# coax-adapter.net
KiCad netlist of a schematic drawn in EAGLE
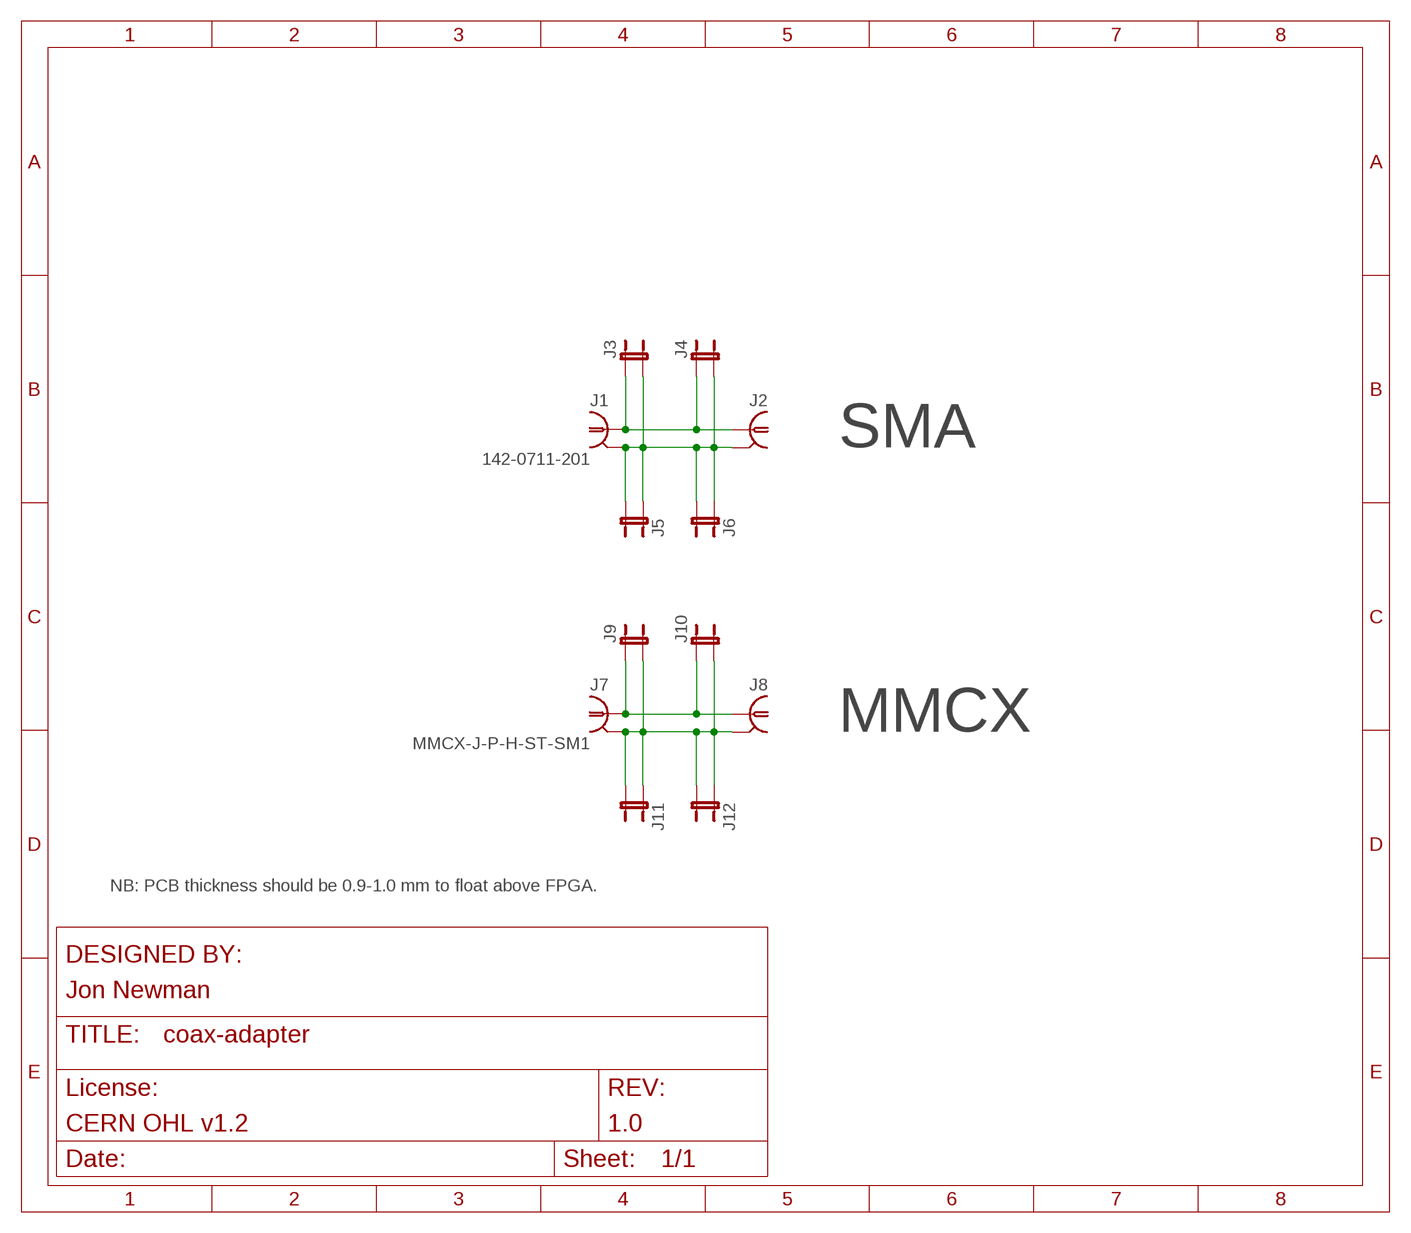
[diagram p0: schematic, sheet 1]

(export (version "E")
  (design (tool "Eeschema 10.0.6"))
  (components
    (comp (ref "J1")
      (value "142-0711-201")
      (footprint "eagle-import:SMA_VERT")
      (libsource (lib "eagle-import") (part "COAX_SMA-VERT-SMA"))
    )
    (comp (ref "J2")
      (value "COAXCOAX-ADAPTER-8X8MM")
      (footprint "eagle-import:COAX-ADAPTER-8X8MM")
      (libsource (lib "eagle-import") (part "COAXCOAX-ADAPTER-8X8MM"))
    )
    (comp (ref "J3")
      (value "JP2E_COAX-ADAPTER-8X8MM-SIG")
      (footprint "eagle-import:COAX-ADAPTER-8X8MM-SIG")
      (libsource (lib "eagle-import") (part "JP2E_COAX-ADAPTER-8X8MM-SIG"))
    )
    (comp (ref "J4")
      (value "JP2E_COAX-ADAPTER-8X8MM-SIG")
      (footprint "eagle-import:COAX-ADAPTER-8X8MM-SIG")
      (libsource (lib "eagle-import") (part "JP2E_COAX-ADAPTER-8X8MM-SIG"))
    )
    (comp (ref "J5")
      (value "JP2E_COAX-ADAPTER-8X8MM-GND")
      (footprint "eagle-import:COAX-ADAPTER-8X8MM-GND")
      (libsource (lib "eagle-import") (part "JP2E_COAX-ADAPTER-8X8MM-GND"))
    )
    (comp (ref "J6")
      (value "JP2E_COAX-ADAPTER-8X8MM-GND")
      (footprint "eagle-import:COAX-ADAPTER-8X8MM-GND")
      (libsource (lib "eagle-import") (part "JP2E_COAX-ADAPTER-8X8MM-GND"))
    )
    (comp (ref "J7")
      (value "MMCX-J-P-H-ST-SM1")
      (footprint "eagle-import:MMCX-SMT-VERT")
      (libsource (lib "eagle-import") (part "COAX_MMCX-VERT"))
    )
    (comp (ref "J8")
      (value "COAXCOAX-ADAPTER-8X8MM")
      (footprint "eagle-import:COAX-ADAPTER-8X8MM")
      (libsource (lib "eagle-import") (part "COAXCOAX-ADAPTER-8X8MM"))
    )
    (comp (ref "J9")
      (value "JP2E_COAX-ADAPTER-8X8MM-SIG")
      (footprint "eagle-import:COAX-ADAPTER-8X8MM-SIG")
      (libsource (lib "eagle-import") (part "JP2E_COAX-ADAPTER-8X8MM-SIG"))
    )
    (comp (ref "J10")
      (value "JP2E_COAX-ADAPTER-8X8MM-SIG")
      (footprint "eagle-import:COAX-ADAPTER-8X8MM-SIG")
      (libsource (lib "eagle-import") (part "JP2E_COAX-ADAPTER-8X8MM-SIG"))
    )
    (comp (ref "J11")
      (value "JP2E_COAX-ADAPTER-8X8MM-GND")
      (footprint "eagle-import:COAX-ADAPTER-8X8MM-GND")
      (libsource (lib "eagle-import") (part "JP2E_COAX-ADAPTER-8X8MM-GND"))
    )
    (comp (ref "J12")
      (value "JP2E_COAX-ADAPTER-8X8MM-GND")
      (footprint "eagle-import:COAX-ADAPTER-8X8MM-GND")
      (libsource (lib "eagle-import") (part "JP2E_COAX-ADAPTER-8X8MM-GND"))
    )
  )
  (nets
    (net (code "1") (name "/ADAPT_SIG") (class "Default")
      (node (ref "J1") (pin "SIG") (pinfunction "1_SIG") (pintype "passive"))
      (node (ref "J10") (pin "SIG") (pinfunction "1_SIG") (pintype "passive"))
      (node (ref "J2") (pin "SIG") (pinfunction "1_SIG") (pintype "passive"))
      (node (ref "J2") (pin "SIGPAD") (pinfunction "1_SIGPAD") (pintype "passive"))
      (node (ref "J3") (pin "SIG") (pinfunction "1_SIG") (pintype "passive"))
      (node (ref "J4") (pin "SIG") (pinfunction "1_SIG") (pintype "passive"))
      (node (ref "J7") (pin "SIG") (pinfunction "1_SIG") (pintype "passive"))
      (node (ref "J8") (pin "SIG") (pinfunction "1_SIG") (pintype "passive"))
      (node (ref "J8") (pin "SIGPAD") (pinfunction "1_SIGPAD") (pintype "passive"))
      (node (ref "J9") (pin "SIG") (pinfunction "1_SIG") (pintype "passive"))
    )
    (net (code "2") (name "/GND") (class "Default")
      (node (ref "J1") (pin "G1") (pinfunction "2_G1") (pintype "passive"))
      (node (ref "J1") (pin "G2") (pinfunction "2_G2") (pintype "passive"))
      (node (ref "J1") (pin "G3") (pinfunction "2_G3") (pintype "passive"))
      (node (ref "J1") (pin "G4") (pinfunction "2_G4") (pintype "passive"))
      (node (ref "J10") (pin "GND1") (pinfunction "2_GND1") (pintype "passive"))
      (node (ref "J10") (pin "GND2") (pinfunction "2_GND2") (pintype "passive"))
      (node (ref "J11") (pin "GND3") (pinfunction "1_GND3") (pintype "passive"))
      (node (ref "J11") (pin "GND4") (pinfunction "2_GND4") (pintype "passive"))
      (node (ref "J12") (pin "GND3") (pinfunction "1_GND3") (pintype "passive"))
      (node (ref "J12") (pin "GND4") (pinfunction "2_GND4") (pintype "passive"))
      (node (ref "J2") (pin "GND1") (pinfunction "2_GND1") (pintype "passive"))
      (node (ref "J2") (pin "GND2") (pinfunction "2_GND2") (pintype "passive"))
      (node (ref "J2") (pin "GND3") (pinfunction "2_GND3") (pintype "passive"))
      (node (ref "J2") (pin "GND4") (pinfunction "2_GND4") (pintype "passive"))
      (node (ref "J3") (pin "GND1") (pinfunction "2_GND1") (pintype "passive"))
      (node (ref "J3") (pin "GND2") (pinfunction "2_GND2") (pintype "passive"))
      (node (ref "J4") (pin "GND1") (pinfunction "2_GND1") (pintype "passive"))
      (node (ref "J4") (pin "GND2") (pinfunction "2_GND2") (pintype "passive"))
      (node (ref "J5") (pin "GND3") (pinfunction "1_GND3") (pintype "passive"))
      (node (ref "J5") (pin "GND4") (pinfunction "2_GND4") (pintype "passive"))
      (node (ref "J6") (pin "GND3") (pinfunction "1_GND3") (pintype "passive"))
      (node (ref "J6") (pin "GND4") (pinfunction "2_GND4") (pintype "passive"))
      (node (ref "J7") (pin "GND@1") (pinfunction "2_GND@1") (pintype "passive"))
      (node (ref "J7") (pin "GND@2") (pinfunction "2_GND@2") (pintype "passive"))
      (node (ref "J7") (pin "GND@3") (pinfunction "2_GND@3") (pintype "passive"))
      (node (ref "J7") (pin "GND@4") (pinfunction "2_GND@4") (pintype "passive"))
      (node (ref "J8") (pin "GND1") (pinfunction "2_GND1") (pintype "passive"))
      (node (ref "J8") (pin "GND2") (pinfunction "2_GND2") (pintype "passive"))
      (node (ref "J8") (pin "GND3") (pinfunction "2_GND3") (pintype "passive"))
      (node (ref "J8") (pin "GND4") (pinfunction "2_GND4") (pintype "passive"))
      (node (ref "J9") (pin "GND1") (pinfunction "2_GND1") (pintype "passive"))
      (node (ref "J9") (pin "GND2") (pinfunction "2_GND2") (pintype "passive"))
    )
  )
)
